# iot_hdmi_mux.net
KiCad netlist of a schematic drawn in Altium Designer
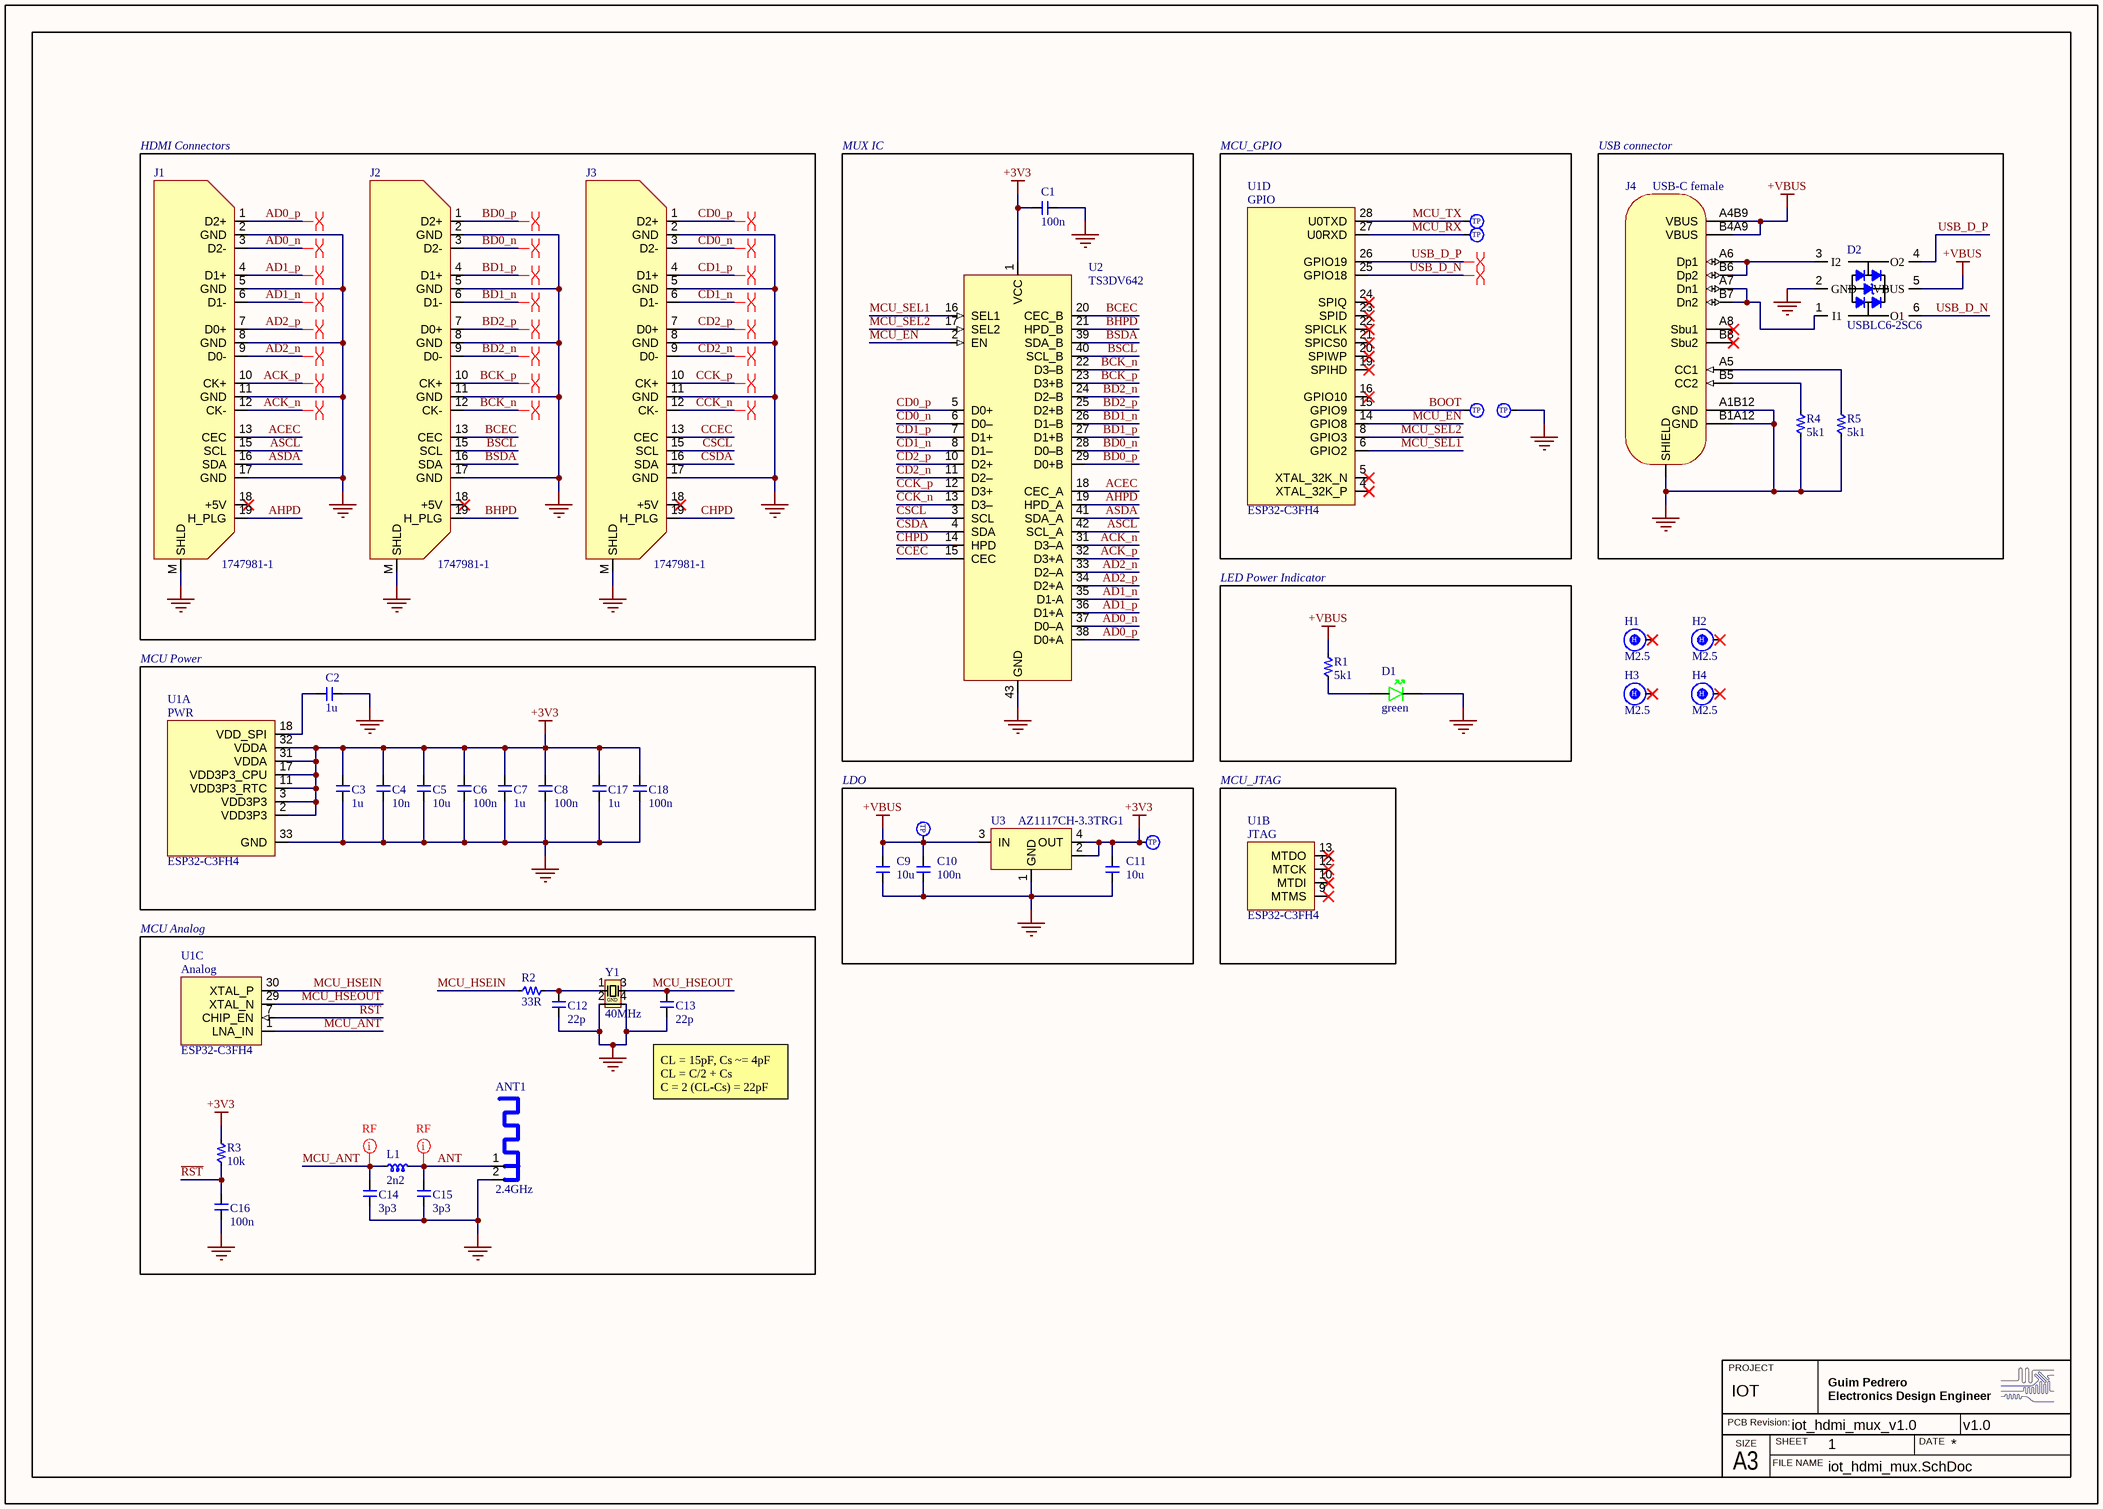
[diagram p0: iot_hdmi_mux.SchDoc]

(export (version "E")
  (design (tool "Eeschema 10.0.6"))
  (components
    (comp (ref "ANT1")
      (value "2.4GHz")
      (footprint "ANT_2.4")
      (description "SWRA117D 2.4GHz antenna design by TI")
      (libsource (lib "iot_hdmi_mux") (part "ANT_2.4"))
    )
    (comp (ref "C1")
      (value "100n")
      (footprint "C0402")
      (description "0402 cap")
      (libsource (lib "iot_hdmi_mux") (part "C_0402"))
    )
    (comp (ref "C2")
      (value "1u")
      (footprint "C0603")
      (description "0603 cap")
      (libsource (lib "iot_hdmi_mux") (part "C_0603"))
    )
    (comp (ref "C3")
      (value "1u")
      (footprint "C0603")
      (description "0603 cap")
      (libsource (lib "iot_hdmi_mux") (part "C_0603"))
    )
    (comp (ref "C4")
      (value "10n")
      (footprint "C0402")
      (description "0402 cap")
      (libsource (lib "iot_hdmi_mux") (part "C_0402"))
    )
    (comp (ref "C5")
      (value "10u")
      (footprint "C0603")
      (description "0603 cap")
      (libsource (lib "iot_hdmi_mux") (part "C_0603"))
    )
    (comp (ref "C6")
      (value "100n")
      (footprint "C0402")
      (description "0402 cap")
      (libsource (lib "iot_hdmi_mux") (part "C_0402"))
    )
    (comp (ref "C7")
      (value "1u")
      (footprint "C0603")
      (description "0603 cap")
      (libsource (lib "iot_hdmi_mux") (part "C_0603"))
    )
    (comp (ref "C8")
      (value "100n")
      (footprint "C0402")
      (description "0402 cap")
      (libsource (lib "iot_hdmi_mux") (part "C_0402"))
    )
    (comp (ref "C9")
      (value "10u")
      (footprint "C0402")
      (description "0402 cap")
      (libsource (lib "LinearDriver") (part "C_0402"))
    )
    (comp (ref "C10")
      (value "100n")
      (footprint "C0402")
      (description "0402 cap")
      (libsource (lib "LinearDriver") (part "C_0402"))
    )
    (comp (ref "C11")
      (value "10u")
      (footprint "C0402")
      (description "0402 cap")
      (libsource (lib "LinearDriver") (part "C_0402"))
    )
    (comp (ref "C12")
      (value "22p")
      (footprint "C0402")
      (description "0402 cap")
      (libsource (lib "FOC_Drive") (part "C_0402"))
    )
    (comp (ref "C13")
      (value "22p")
      (footprint "C0402")
      (description "0402 cap")
      (libsource (lib "FOC_Drive") (part "C_0402"))
    )
    (comp (ref "C14")
      (value "3p3")
      (footprint "C0402")
      (description "0402 cap")
      (libsource (lib "iot_hdmi_mux") (part "C_0402"))
    )
    (comp (ref "C15")
      (value "3p3")
      (footprint "C0402")
      (description "0402 cap")
      (libsource (lib "iot_hdmi_mux") (part "C_0402"))
    )
    (comp (ref "C16")
      (value "100n")
      (footprint "C0402")
      (description "0402 cap")
      (libsource (lib "iot_hdmi_mux") (part "C_0402"))
    )
    (comp (ref "C17")
      (value "1u")
      (footprint "C0603")
      (description "0603 cap")
      (libsource (lib "iot_hdmi_mux") (part "C_0603"))
    )
    (comp (ref "C18")
      (value "100n")
      (footprint "C0402")
      (description "0402 cap")
      (libsource (lib "iot_hdmi_mux") (part "C_0402"))
    )
    (comp (ref "D1")
      (value "green")
      (footprint "LED_0805_G")
      (description "0805 green LED")
      (libsource (lib "iot_hdmi_mux") (part "LED_0805_G"))
    )
    (comp (ref "D2")
      (value "USBLC6-2SC6")
      (footprint "USBLC6-2SC6")
      (description "Trans Voltage Suppressor Diode, 5V V(RWM), Unidirectional, 1 Element, Silicon")
      (fields (field (name "MANUFACTURER") "STMicroelectronics"))
      (libsource (lib "R20_PCBM") (part "USBLC6-2SC6"))
    )
    (comp (ref "H1")
      (value "M2.5")
      (footprint "M2.5_HOLE")
      (description "M2.5 hole with connection")
      (libsource (lib "iot_hdmi_mux") (part "M2.5_HOLE"))
    )
    (comp (ref "H2")
      (value "M2.5")
      (footprint "M2.5_HOLE")
      (description "M2.5 hole with connection")
      (libsource (lib "iot_hdmi_mux") (part "M2.5_HOLE"))
    )
    (comp (ref "H3")
      (value "M2.5")
      (footprint "M2.5_HOLE")
      (description "M2.5 hole with connection")
      (libsource (lib "iot_hdmi_mux") (part "M2.5_HOLE"))
    )
    (comp (ref "H4")
      (value "M2.5")
      (footprint "M2.5_HOLE")
      (description "M2.5 hole with connection")
      (libsource (lib "iot_hdmi_mux") (part "M2.5_HOLE"))
    )
    (comp (ref "J1")
      (value "1747981-1")
      (footprint "1747981-1")
      (description "HDMI (High-Definition Multimedia Interface) Connector; No Flange; Through hole")
      (fields (field (name "MANUFACTURER") "AMP - TE CONNECTIVITY"))
      (libsource (lib "iot_hdmi_mux") (part "1747981-1"))
    )
    (comp (ref "J2")
      (value "1747981-1")
      (footprint "1747981-1")
      (description "HDMI (High-Definition Multimedia Interface) Connector; No Flange; Through hole")
      (fields (field (name "MANUFACTURER") "AMP - TE CONNECTIVITY"))
      (libsource (lib "iot_hdmi_mux") (part "1747981-1"))
    )
    (comp (ref "J3")
      (value "1747981-1")
      (footprint "1747981-1")
      (description "HDMI (High-Definition Multimedia Interface) Connector; No Flange; Through hole")
      (fields (field (name "MANUFACTURER") "AMP - TE CONNECTIVITY"))
      (libsource (lib "iot_hdmi_mux") (part "1747981-1"))
    )
    (comp (ref "J4")
      (value "USB-C female")
      (footprint "TYPE-C-31-M-12")
      (description "Conn USB Type C PL 22 POS 0.5mm Solder ST SMD 22 Terminal 1Port Emboss T/R")
      (fields
        (field (name "MANUFACTURER") "HRO Electronics")
        (field (name "MANUFACTURER PART NUMBER") "TYPE-C-31-M-12")
      )
      (libsource (lib "rotor_magnetics_tb") (part "TYPE-C-31-M-12"))
    )
    (comp (ref "L1")
      (value "2n2")
      (footprint "L0402")
      (description "0402 inductor")
      (libsource (lib "iot_hdmi_mux") (part "L_0402"))
    )
    (comp (ref "R1")
      (value "5k1")
      (footprint "R0402")
      (description "0402 62.5mW")
      (libsource (lib "PCB_motor") (part "R_0402"))
    )
    (comp (ref "R2")
      (value "33R")
      (footprint "R0402")
      (description "0402 62.5mW")
      (libsource (lib "iot_hdmi_mux") (part "R_0402"))
    )
    (comp (ref "R3")
      (value "10k")
      (footprint "R0402")
      (description "0402 62.5mW")
      (libsource (lib "iot_hdmi_mux") (part "R_0402"))
    )
    (comp (ref "R4")
      (value "5k1")
      (footprint "R0402")
      (description "0402 62.5mW")
      (libsource (lib "PCB_motor") (part "R_0402"))
    )
    (comp (ref "R5")
      (value "5k1")
      (footprint "R0402")
      (description "0402 62.5mW")
      (libsource (lib "PCB_motor") (part "R_0402"))
    )
    (comp (ref "TP1")
      (value "Testing_Point_1mm")
      (footprint "TestingPoint_1mm")
      (description "1mm testing point")
      (libsource (lib "iot_hdmi_mux") (part "Testing_Point_1mm"))
    )
    (comp (ref "TP2")
      (value "Testing_Point_1mm")
      (footprint "TestingPoint_1mm")
      (description "1mm testing point")
      (libsource (lib "iot_hdmi_mux") (part "Testing_Point_1mm"))
    )
    (comp (ref "TP3")
      (value "Testing_Point_1mm")
      (footprint "TestingPoint_1mm")
      (description "1mm testing point")
      (libsource (lib "iot_hdmi_mux") (part "Testing_Point_1mm"))
    )
    (comp (ref "TP4")
      (value "Testing_Point_1mm")
      (footprint "TestingPoint_1mm")
      (description "1mm testing point")
      (libsource (lib "iot_hdmi_mux") (part "Testing_Point_1mm"))
    )
    (comp (ref "TP5")
      (value "Testing_Point_1mm")
      (footprint "TestingPoint_1mm")
      (description "1mm testing point")
      (libsource (lib "LinearDriver") (part "Testing_Point_1mm"))
    )
    (comp (ref "TP6")
      (value "Testing_Point_1mm")
      (footprint "TestingPoint_1mm")
      (description "1mm testing point")
      (libsource (lib "LinearDriver") (part "Testing_Point_1mm"))
    )
    (comp (ref "U1")
      (value "ESP32-C3FH4")
      (footprint "QFN50P500X500X90_HS-33N")
      (fields (field (name "MANUFACTURER") "Espressif Systems"))
      (libsource (lib "iot_hdmi_mux") (part "ESP32-C3FH4"))
    )
    (comp (ref "U2")
      (value "TS3DV642")
      (footprint "QFN50P350X900X80_HS-43N")
      (description "6-Gbps 12-channel differential 1-to-2 and 2-to-1 mux for DVI 1.0/ DisplayPort 1.4 /HDMI 2.0")
      (fields
        (field (name "MANUFACTURER") "Texas Instruments")
        (field (name "MANUFACTURER PART NUMBER") "TS3DV642A0RUAR")
      )
      (libsource (lib "iot_hdmi_mux") (part "TS3DV642"))
    )
    (comp (ref "U3")
      (value "AZ1117CH-3.3TRG1")
      (footprint "AZ1117CH-3.3TRG1")
      (description "Fixed Positive LDO Regulator, 3.3V, 1.3V Dropout, BIPolar, PDSO3")
      (fields (field (name "MANUFACTURER") "Diodes"))
      (libsource (lib "LinearDriver") (part "AZ1117CH-3.3TRG1"))
    )
    (comp (ref "Y1")
      (value "40MHz")
      (footprint "SMD3225-4P")
      (description "40MHz Surface Mount Crystal 15pF ±10ppm ±20ppm SMD3225-4P Crystals ROHS")
      (libsource (lib "iot_hdmi_mux") (part "X322540MPB4SI"))
    )
  )
  (nets
    (net (code "1") (name "+3V3") (class "Default")
      (node (ref "C1") (pin "2") (pinfunction "2_2") (pintype "passive"))
      (node (ref "C11") (pin "2") (pinfunction "2_2") (pintype "passive"))
      (node (ref "C17") (pin "2") (pinfunction "2_2") (pintype "passive"))
      (node (ref "C18") (pin "1") (pinfunction "1_1") (pintype "passive"))
      (node (ref "C3") (pin "2") (pinfunction "2_2") (pintype "passive"))
      (node (ref "C4") (pin "1") (pinfunction "1_1") (pintype "passive"))
      (node (ref "C5") (pin "2") (pinfunction "2_2") (pintype "passive"))
      (node (ref "C6") (pin "1") (pinfunction "1_1") (pintype "passive"))
      (node (ref "C7") (pin "2") (pinfunction "2_2") (pintype "passive"))
      (node (ref "C8") (pin "1") (pinfunction "1_1") (pintype "passive"))
      (node (ref "R3") (pin "2") (pinfunction "2_2") (pintype "passive"))
      (node (ref "TP6") (pin "1") (pinfunction "1_1") (pintype "passive"))
      (node (ref "U1") (pin "11") (pinfunction "VDD3P3_RTC_11") (pintype "power_in"))
      (node (ref "U1") (pin "17") (pinfunction "VDD3P3_CPU_17") (pintype "power_in"))
      (node (ref "U1") (pin "2") (pinfunction "VDD3P3_2") (pintype "power_in"))
      (node (ref "U1") (pin "3") (pinfunction "VDD3P3_3") (pintype "power_in"))
      (node (ref "U1") (pin "31") (pinfunction "VDDA_31") (pintype "power_in"))
      (node (ref "U1") (pin "32") (pinfunction "VDDA_32") (pintype "power_in"))
      (node (ref "U2") (pin "1") (pinfunction "VCC_1") (pintype "power_in"))
      (node (ref "U3") (pin "2") (pinfunction "OUT_2") (pintype "power_in"))
      (node (ref "U3") (pin "4") (pinfunction "OUT_4") (pintype "power_in"))
    )
    (net (code "2") (name "+VBUS") (class "Default")
      (node (ref "C10") (pin "2") (pinfunction "2_2") (pintype "passive"))
      (node (ref "C9") (pin "2") (pinfunction "2_2") (pintype "passive"))
      (node (ref "D2") (pin "5") (pinfunction "VBUS_5") (pintype "passive"))
      (node (ref "J4") (pin "A4B9") (pinfunction "VBUS_A4B9") (pintype "power_in"))
      (node (ref "J4") (pin "B4A9") (pinfunction "VBUS_B4A9") (pintype "power_in"))
      (node (ref "R1") (pin "2") (pinfunction "2_2") (pintype "passive"))
      (node (ref "TP5") (pin "1") (pinfunction "1_1") (pintype "passive"))
      (node (ref "U3") (pin "3") (pinfunction "IN_3") (pintype "power_in"))
    )
    (net (code "3") (name "/ACEC") (class "Default")
      (node (ref "J1") (pin "13") (pinfunction "CEC_13") (pintype "bidirectional"))
      (node (ref "U2") (pin "18") (pinfunction "CEC_A_18") (pintype "bidirectional"))
    )
    (net (code "4") (name "/ACK_n") (class "Default")
      (node (ref "J1") (pin "12") (pinfunction "CK-_12") (pintype "bidirectional"))
      (node (ref "U2") (pin "31") (pinfunction "D3–A_31") (pintype "bidirectional"))
    )
    (net (code "5") (name "/ACK_p") (class "Default")
      (node (ref "J1") (pin "10") (pinfunction "CK+_10") (pintype "bidirectional"))
      (node (ref "U2") (pin "32") (pinfunction "D3+A_32") (pintype "bidirectional"))
    )
    (net (code "6") (name "/AD0_n") (class "Default")
      (node (ref "J1") (pin "3") (pinfunction "D2-_3") (pintype "bidirectional"))
      (node (ref "U2") (pin "37") (pinfunction "D0–A_37") (pintype "bidirectional"))
    )
    (net (code "7") (name "/AD0_p") (class "Default")
      (node (ref "J1") (pin "1") (pinfunction "D2+_1") (pintype "bidirectional"))
      (node (ref "U2") (pin "38") (pinfunction "D0+A_38") (pintype "bidirectional"))
    )
    (net (code "8") (name "/AD1_n") (class "Default")
      (node (ref "J1") (pin "6") (pinfunction "D1-_6") (pintype "bidirectional"))
      (node (ref "U2") (pin "35") (pinfunction "D1-A_35") (pintype "bidirectional"))
    )
    (net (code "9") (name "/AD1_p") (class "Default")
      (node (ref "J1") (pin "4") (pinfunction "D1+_4") (pintype "bidirectional"))
      (node (ref "U2") (pin "36") (pinfunction "D1+A_36") (pintype "bidirectional"))
    )
    (net (code "10") (name "/AD2_n") (class "Default")
      (node (ref "J1") (pin "9") (pinfunction "D0-_9") (pintype "bidirectional"))
      (node (ref "U2") (pin "33") (pinfunction "D2–A_33") (pintype "bidirectional"))
    )
    (net (code "11") (name "/AD2_p") (class "Default")
      (node (ref "J1") (pin "7") (pinfunction "D0+_7") (pintype "bidirectional"))
      (node (ref "U2") (pin "34") (pinfunction "D2+A_34") (pintype "bidirectional"))
    )
    (net (code "12") (name "/AHPD") (class "Default")
      (node (ref "J1") (pin "19") (pinfunction "H_PLG_19") (pintype "bidirectional"))
      (node (ref "U2") (pin "19") (pinfunction "HPD_A_19") (pintype "bidirectional"))
    )
    (net (code "13") (name "/ANT") (class "Default")
      (node (ref "ANT1") (pin "1") (pinfunction "1_1") (pintype "passive"))
      (node (ref "C15") (pin "1") (pinfunction "1_1") (pintype "passive"))
      (node (ref "L1") (pin "2") (pinfunction "2_2") (pintype "passive"))
    )
    (net (code "14") (name "/ASCL") (class "Default")
      (node (ref "J1") (pin "15") (pinfunction "SCL_15") (pintype "bidirectional"))
      (node (ref "U2") (pin "42") (pinfunction "SCL_A_42") (pintype "bidirectional"))
    )
    (net (code "15") (name "/ASDA") (class "Default")
      (node (ref "J1") (pin "16") (pinfunction "SDA_16") (pintype "bidirectional"))
      (node (ref "U2") (pin "41") (pinfunction "SDA_A_41") (pintype "bidirectional"))
    )
    (net (code "16") (name "/BCEC") (class "Default")
      (node (ref "J2") (pin "13") (pinfunction "CEC_13") (pintype "bidirectional"))
      (node (ref "U2") (pin "20") (pinfunction "CEC_B_20") (pintype "bidirectional"))
    )
    (net (code "17") (name "/BCK_n") (class "Default")
      (node (ref "J2") (pin "12") (pinfunction "CK-_12") (pintype "bidirectional"))
      (node (ref "U2") (pin "22") (pinfunction "D3–B_22") (pintype "bidirectional"))
    )
    (net (code "18") (name "/BCK_p") (class "Default")
      (node (ref "J2") (pin "10") (pinfunction "CK+_10") (pintype "bidirectional"))
      (node (ref "U2") (pin "23") (pinfunction "D3+B_23") (pintype "bidirectional"))
    )
    (net (code "19") (name "/BD0_n") (class "Default")
      (node (ref "J2") (pin "3") (pinfunction "D2-_3") (pintype "bidirectional"))
      (node (ref "U2") (pin "28") (pinfunction "D0–B_28") (pintype "bidirectional"))
    )
    (net (code "20") (name "/BD0_p") (class "Default")
      (node (ref "J2") (pin "1") (pinfunction "D2+_1") (pintype "bidirectional"))
      (node (ref "U2") (pin "29") (pinfunction "D0+B_29") (pintype "bidirectional"))
    )
    (net (code "21") (name "/BD1_n") (class "Default")
      (node (ref "J2") (pin "6") (pinfunction "D1-_6") (pintype "bidirectional"))
      (node (ref "U2") (pin "26") (pinfunction "D1–B_26") (pintype "bidirectional"))
    )
    (net (code "22") (name "/BD1_p") (class "Default")
      (node (ref "J2") (pin "4") (pinfunction "D1+_4") (pintype "bidirectional"))
      (node (ref "U2") (pin "27") (pinfunction "D1+B_27") (pintype "bidirectional"))
    )
    (net (code "23") (name "/BD2_n") (class "Default")
      (node (ref "J2") (pin "9") (pinfunction "D0-_9") (pintype "bidirectional"))
      (node (ref "U2") (pin "24") (pinfunction "D2–B_24") (pintype "bidirectional"))
    )
    (net (code "24") (name "/BD2_p") (class "Default")
      (node (ref "J2") (pin "7") (pinfunction "D0+_7") (pintype "bidirectional"))
      (node (ref "U2") (pin "25") (pinfunction "D2+B_25") (pintype "bidirectional"))
    )
    (net (code "25") (name "/BHPD") (class "Default")
      (node (ref "J2") (pin "19") (pinfunction "H_PLG_19") (pintype "bidirectional"))
      (node (ref "U2") (pin "21") (pinfunction "HPD_B_21") (pintype "bidirectional"))
    )
    (net (code "26") (name "/BOOT") (class "Default")
      (node (ref "TP3") (pin "1") (pinfunction "1_1") (pintype "passive"))
      (node (ref "U1") (pin "15") (pinfunction "GPIO9_15") (pintype "bidirectional"))
    )
    (net (code "27") (name "/BSCL") (class "Default")
      (node (ref "J2") (pin "15") (pinfunction "SCL_15") (pintype "bidirectional"))
      (node (ref "U2") (pin "40") (pinfunction "SCL_B_40") (pintype "bidirectional"))
    )
    (net (code "28") (name "/BSDA") (class "Default")
      (node (ref "J2") (pin "16") (pinfunction "SDA_16") (pintype "bidirectional"))
      (node (ref "U2") (pin "39") (pinfunction "SDA_B_39") (pintype "bidirectional"))
    )
    (net (code "29") (name "/CCEC") (class "Default")
      (node (ref "J3") (pin "13") (pinfunction "CEC_13") (pintype "bidirectional"))
      (node (ref "U2") (pin "15") (pinfunction "CEC_15") (pintype "bidirectional"))
    )
    (net (code "30") (name "/CCK_n") (class "Default")
      (node (ref "J3") (pin "12") (pinfunction "CK-_12") (pintype "bidirectional"))
      (node (ref "U2") (pin "13") (pinfunction "D3–_13") (pintype "bidirectional"))
    )
    (net (code "31") (name "/CCK_p") (class "Default")
      (node (ref "J3") (pin "10") (pinfunction "CK+_10") (pintype "bidirectional"))
      (node (ref "U2") (pin "12") (pinfunction "D3+_12") (pintype "bidirectional"))
    )
    (net (code "32") (name "/CD0_n") (class "Default")
      (node (ref "J3") (pin "3") (pinfunction "D2-_3") (pintype "bidirectional"))
      (node (ref "U2") (pin "6") (pinfunction "D0–_6") (pintype "bidirectional"))
    )
    (net (code "33") (name "/CD0_p") (class "Default")
      (node (ref "J3") (pin "1") (pinfunction "D2+_1") (pintype "bidirectional"))
      (node (ref "U2") (pin "5") (pinfunction "D0+_5") (pintype "bidirectional"))
    )
    (net (code "34") (name "/CD1_n") (class "Default")
      (node (ref "J3") (pin "6") (pinfunction "D1-_6") (pintype "bidirectional"))
      (node (ref "U2") (pin "8") (pinfunction "D1–_8") (pintype "bidirectional"))
    )
    (net (code "35") (name "/CD1_p") (class "Default")
      (node (ref "J3") (pin "4") (pinfunction "D1+_4") (pintype "bidirectional"))
      (node (ref "U2") (pin "7") (pinfunction "D1+_7") (pintype "bidirectional"))
    )
    (net (code "36") (name "/CD2_n") (class "Default")
      (node (ref "J3") (pin "9") (pinfunction "D0-_9") (pintype "bidirectional"))
      (node (ref "U2") (pin "11") (pinfunction "D2–_11") (pintype "bidirectional"))
    )
    (net (code "37") (name "/CD2_p") (class "Default")
      (node (ref "J3") (pin "7") (pinfunction "D0+_7") (pintype "bidirectional"))
      (node (ref "U2") (pin "10") (pinfunction "D2+_10") (pintype "bidirectional"))
    )
    (net (code "38") (name "/CHPD") (class "Default")
      (node (ref "J3") (pin "19") (pinfunction "H_PLG_19") (pintype "bidirectional"))
      (node (ref "U2") (pin "14") (pinfunction "HPD_14") (pintype "bidirectional"))
    )
    (net (code "39") (name "/CSCL") (class "Default")
      (node (ref "J3") (pin "15") (pinfunction "SCL_15") (pintype "bidirectional"))
      (node (ref "U2") (pin "3") (pinfunction "SCL_3") (pintype "bidirectional"))
    )
    (net (code "40") (name "/CSDA") (class "Default")
      (node (ref "J3") (pin "16") (pinfunction "SDA_16") (pintype "bidirectional"))
      (node (ref "U2") (pin "4") (pinfunction "SDA_4") (pintype "bidirectional"))
    )
    (net (code "41") (name "/MCU_ANT") (class "Default")
      (node (ref "C14") (pin "1") (pinfunction "1_1") (pintype "passive"))
      (node (ref "L1") (pin "1") (pinfunction "1_1") (pintype "passive"))
      (node (ref "U1") (pin "1") (pinfunction "LNA_IN_1") (pintype "bidirectional"))
    )
    (net (code "42") (name "/MCU_EN") (class "Default")
      (node (ref "U1") (pin "14") (pinfunction "GPIO8_14") (pintype "bidirectional"))
      (node (ref "U2") (pin "2") (pinfunction "EN_2") (pintype "input"))
    )
    (net (code "43") (name "/MCU_HSEIN") (class "Default")
      (node (ref "R2") (pin "1") (pinfunction "1_1") (pintype "passive"))
      (node (ref "U1") (pin "30") (pinfunction "XTAL_P_30") (pintype "bidirectional"))
    )
    (net (code "44") (name "/MCU_HSEOUT") (class "Default")
      (node (ref "C13") (pin "2") (pinfunction "2_2") (pintype "passive"))
      (node (ref "U1") (pin "29") (pinfunction "XTAL_N_29") (pintype "bidirectional"))
      (node (ref "Y1") (pin "3") (pinfunction "3_3") (pintype "passive"))
    )
    (net (code "45") (name "/MCU_RX") (class "Default")
      (node (ref "TP2") (pin "1") (pinfunction "1_1") (pintype "passive"))
      (node (ref "U1") (pin "27") (pinfunction "U0RXD_27") (pintype "bidirectional"))
    )
    (net (code "46") (name "/MCU_SEL1") (class "Default")
      (node (ref "U1") (pin "6") (pinfunction "GPIO2_6") (pintype "bidirectional"))
      (node (ref "U2") (pin "16") (pinfunction "SEL1_16") (pintype "input"))
    )
    (net (code "47") (name "/MCU_SEL2") (class "Default")
      (node (ref "U1") (pin "8") (pinfunction "GPIO3_8") (pintype "bidirectional"))
      (node (ref "U2") (pin "17") (pinfunction "SEL2_17") (pintype "input"))
    )
    (net (code "48") (name "/MCU_TX") (class "Default")
      (node (ref "TP1") (pin "1") (pinfunction "1_1") (pintype "passive"))
      (node (ref "U1") (pin "28") (pinfunction "U0TXD_28") (pintype "bidirectional"))
    )
    (net (code "49") (name "/USB_D_N") (class "Default")
      (node (ref "D2") (pin "6") (pinfunction "O1_6") (pintype "passive"))
      (node (ref "U1") (pin "25") (pinfunction "GPIO18_25") (pintype "bidirectional"))
    )
    (net (code "50") (name "/USB_D_P") (class "Default")
      (node (ref "D2") (pin "4") (pinfunction "O2_4") (pintype "passive"))
      (node (ref "U1") (pin "26") (pinfunction "GPIO19_26") (pintype "bidirectional"))
    )
    (net (code "51") (name "/~{RST}") (class "Default")
      (node (ref "C16") (pin "1") (pinfunction "1_1") (pintype "passive"))
      (node (ref "R3") (pin "1") (pinfunction "1_1") (pintype "passive"))
      (node (ref "U1") (pin "7") (pinfunction "CHIP_EN_7") (pintype "input"))
    )
    (net (code "52") (name "GND") (class "Default")
      (node (ref "ANT1") (pin "2") (pinfunction "2_2") (pintype "passive"))
      (node (ref "C1") (pin "1") (pinfunction "1_1") (pintype "passive"))
      (node (ref "C10") (pin "1") (pinfunction "1_1") (pintype "passive"))
      (node (ref "C11") (pin "1") (pinfunction "1_1") (pintype "passive"))
      (node (ref "C12") (pin "1") (pinfunction "1_1") (pintype "passive"))
      (node (ref "C13") (pin "1") (pinfunction "1_1") (pintype "passive"))
      (node (ref "C14") (pin "2") (pinfunction "2_2") (pintype "passive"))
      (node (ref "C15") (pin "2") (pinfunction "2_2") (pintype "passive"))
      (node (ref "C16") (pin "2") (pinfunction "2_2") (pintype "passive"))
      (node (ref "C17") (pin "1") (pinfunction "1_1") (pintype "passive"))
      (node (ref "C18") (pin "2") (pinfunction "2_2") (pintype "passive"))
      (node (ref "C2") (pin "1") (pinfunction "1_1") (pintype "passive"))
      (node (ref "C3") (pin "1") (pinfunction "1_1") (pintype "passive"))
      (node (ref "C4") (pin "2") (pinfunction "2_2") (pintype "passive"))
      (node (ref "C5") (pin "1") (pinfunction "1_1") (pintype "passive"))
      (node (ref "C6") (pin "2") (pinfunction "2_2") (pintype "passive"))
      (node (ref "C7") (pin "1") (pinfunction "1_1") (pintype "passive"))
      (node (ref "C8") (pin "2") (pinfunction "2_2") (pintype "passive"))
      (node (ref "C9") (pin "1") (pinfunction "1_1") (pintype "passive"))
      (node (ref "D1") (pin "1") (pinfunction "1_1") (pintype "passive"))
      (node (ref "D2") (pin "2") (pinfunction "GND_2") (pintype "passive"))
      (node (ref "J1") (pin "11") (pinfunction "GND_11") (pintype "power_in"))
      (node (ref "J1") (pin "17") (pinfunction "GND_17") (pintype "power_in"))
      (node (ref "J1") (pin "2") (pinfunction "GND_2") (pintype "power_in"))
      (node (ref "J1") (pin "5") (pinfunction "GND_5") (pintype "power_in"))
      (node (ref "J1") (pin "8") (pinfunction "GND_8") (pintype "power_in"))
      (node (ref "J1") (pin "M") (pinfunction "SHLD_M") (pintype "power_in"))
      (node (ref "J2") (pin "11") (pinfunction "GND_11") (pintype "power_in"))
      (node (ref "J2") (pin "17") (pinfunction "GND_17") (pintype "power_in"))
      (node (ref "J2") (pin "2") (pinfunction "GND_2") (pintype "power_in"))
      (node (ref "J2") (pin "5") (pinfunction "GND_5") (pintype "power_in"))
      (node (ref "J2") (pin "8") (pinfunction "GND_8") (pintype "power_in"))
      (node (ref "J2") (pin "M") (pinfunction "SHLD_M") (pintype "power_in"))
      (node (ref "J3") (pin "11") (pinfunction "GND_11") (pintype "power_in"))
      (node (ref "J3") (pin "17") (pinfunction "GND_17") (pintype "power_in"))
      (node (ref "J3") (pin "2") (pinfunction "GND_2") (pintype "power_in"))
      (node (ref "J3") (pin "5") (pinfunction "GND_5") (pintype "power_in"))
      (node (ref "J3") (pin "8") (pinfunction "GND_8") (pintype "power_in"))
      (node (ref "J3") (pin "M") (pinfunction "SHLD_M") (pintype "power_in"))
      (node (ref "J4") (pin "A1B12") (pinfunction "GND_A1B12") (pintype "power_in"))
      (node (ref "J4") (pin "B1A12") (pinfunction "GND_B1A12") (pintype "power_in"))
      (node (ref "J4") (pin "M1") (pinfunction "SHIELD_M1") (pintype "passive"))
      (node (ref "R4") (pin "1") (pinfunction "1_1") (pintype "passive"))
      (node (ref "R5") (pin "1") (pinfunction "1_1") (pintype "passive"))
      (node (ref "TP4") (pin "1") (pinfunction "1_1") (pintype "passive"))
      (node (ref "U1") (pin "33") (pinfunction "GND_33") (pintype "power_in"))
      (node (ref "U2") (pin "43") (pinfunction "GND_43") (pintype "power_in"))
      (node (ref "U3") (pin "1") (pinfunction "GND_1") (pintype "power_in"))
      (node (ref "Y1") (pin "2") (pinfunction "2_2") (pintype "passive"))
      (node (ref "Y1") (pin "4") (pinfunction "4_4") (pintype "passive"))
    )
    (net (code "53") (name "Net-(C12-Pad2)") (class "Default")
      (node (ref "C12") (pin "2") (pinfunction "2_2") (pintype "passive"))
      (node (ref "R2") (pin "2") (pinfunction "2_2") (pintype "passive"))
      (node (ref "Y1") (pin "1") (pinfunction "1_1") (pintype "passive"))
    )
    (net (code "54") (name "Net-(D1-Pad2)") (class "Default")
      (node (ref "D1") (pin "2") (pinfunction "2_2") (pintype "passive"))
      (node (ref "R1") (pin "1") (pinfunction "1_1") (pintype "passive"))
    )
    (net (code "55") (name "Net-(D2-I1)") (class "Default")
      (node (ref "D2") (pin "1") (pinfunction "I1_1") (pintype "passive"))
      (node (ref "J4") (pin "A7") (pinfunction "Dn1_A7") (pintype "bidirectional"))
      (node (ref "J4") (pin "B7") (pinfunction "Dn2_B7") (pintype "bidirectional"))
    )
    (net (code "56") (name "Net-(D2-I2)") (class "Default")
      (node (ref "D2") (pin "3") (pinfunction "I2_3") (pintype "passive"))
      (node (ref "J4") (pin "A6") (pinfunction "Dp1_A6") (pintype "bidirectional"))
      (node (ref "J4") (pin "B6") (pinfunction "Dp2_B6") (pintype "bidirectional"))
    )
    (net (code "57") (name "Net-(J4-CC1)") (class "Default")
      (node (ref "J4") (pin "A5") (pinfunction "CC1_A5") (pintype "input"))
      (node (ref "R5") (pin "2") (pinfunction "2_2") (pintype "passive"))
    )
    (net (code "58") (name "Net-(J4-CC2)") (class "Default")
      (node (ref "J4") (pin "B5") (pinfunction "CC2_B5") (pintype "input"))
      (node (ref "R4") (pin "2") (pinfunction "2_2") (pintype "passive"))
    )
    (net (code "59") (name "Net-(U1A-VDD_SPI)") (class "Default")
      (node (ref "C2") (pin "2") (pinfunction "2_2") (pintype "passive"))
      (node (ref "U1") (pin "18") (pinfunction "VDD_SPI_18") (pintype "power_in"))
    )
    (net (code "60") (name "unconnected-(H1-Pad1)") (class "Default")
      (node (ref "H1") (pin "1") (pinfunction "1_1") (pintype "passive+no_connect"))
    )
    (net (code "61") (name "unconnected-(H2-Pad1)") (class "Default")
      (node (ref "H2") (pin "1") (pinfunction "1_1") (pintype "passive+no_connect"))
    )
    (net (code "62") (name "unconnected-(H3-Pad1)") (class "Default")
      (node (ref "H3") (pin "1") (pinfunction "1_1") (pintype "passive+no_connect"))
    )
    (net (code "63") (name "unconnected-(H4-Pad1)") (class "Default")
      (node (ref "H4") (pin "1") (pinfunction "1_1") (pintype "passive+no_connect"))
    )
    (net (code "64") (name "unconnected-(J1-+5V-Pad18)") (class "Default")
      (node (ref "J1") (pin "18") (pinfunction "+5V_18") (pintype "power_in+no_connect"))
    )
    (net (code "65") (name "unconnected-(J2-+5V-Pad18)") (class "Default")
      (node (ref "J2") (pin "18") (pinfunction "+5V_18") (pintype "power_in+no_connect"))
    )
    (net (code "66") (name "unconnected-(J3-+5V-Pad18)") (class "Default")
      (node (ref "J3") (pin "18") (pinfunction "+5V_18") (pintype "power_in+no_connect"))
    )
    (net (code "67") (name "unconnected-(J4-Sbu1-PadA8)") (class "Default")
      (node (ref "J4") (pin "A8") (pinfunction "Sbu1_A8") (pintype "passive+no_connect"))
    )
    (net (code "68") (name "unconnected-(J4-Sbu2-PadB8)") (class "Default")
      (node (ref "J4") (pin "B8") (pinfunction "Sbu2_B8") (pintype "passive+no_connect"))
    )
    (net (code "69") (name "unconnected-(U1B-MTCK-Pad12)") (class "Default")
      (node (ref "U1") (pin "12") (pinfunction "MTCK_12") (pintype "bidirectional+no_connect"))
    )
    (net (code "70") (name "unconnected-(U1B-MTDI-Pad10)") (class "Default")
      (node (ref "U1") (pin "10") (pinfunction "MTDI_10") (pintype "bidirectional+no_connect"))
    )
    (net (code "71") (name "unconnected-(U1B-MTDO-Pad13)") (class "Default")
      (node (ref "U1") (pin "13") (pinfunction "MTDO_13") (pintype "bidirectional+no_connect"))
    )
    (net (code "72") (name "unconnected-(U1B-MTMS-Pad9)") (class "Default")
      (node (ref "U1") (pin "9") (pinfunction "MTMS_9") (pintype "bidirectional+no_connect"))
    )
    (net (code "73") (name "unconnected-(U1D-GPIO10-Pad16)") (class "Default")
      (node (ref "U1") (pin "16") (pinfunction "GPIO10_16") (pintype "bidirectional+no_connect"))
    )
    (net (code "74") (name "unconnected-(U1D-SPICLK-Pad22)") (class "Default")
      (node (ref "U1") (pin "22") (pinfunction "SPICLK_22") (pintype "bidirectional+no_connect"))
    )
    (net (code "75") (name "unconnected-(U1D-SPICS0-Pad21)") (class "Default")
      (node (ref "U1") (pin "21") (pinfunction "SPICS0_21") (pintype "bidirectional+no_connect"))
    )
    (net (code "76") (name "unconnected-(U1D-SPID-Pad23)") (class "Default")
      (node (ref "U1") (pin "23") (pinfunction "SPID_23") (pintype "bidirectional+no_connect"))
    )
    (net (code "77") (name "unconnected-(U1D-SPIHD-Pad19)") (class "Default")
      (node (ref "U1") (pin "19") (pinfunction "SPIHD_19") (pintype "bidirectional+no_connect"))
    )
    (net (code "78") (name "unconnected-(U1D-SPIQ-Pad24)") (class "Default")
      (node (ref "U1") (pin "24") (pinfunction "SPIQ_24") (pintype "bidirectional+no_connect"))
    )
    (net (code "79") (name "unconnected-(U1D-SPIWP-Pad20)") (class "Default")
      (node (ref "U1") (pin "20") (pinfunction "SPIWP_20") (pintype "bidirectional+no_connect"))
    )
    (net (code "80") (name "unconnected-(U1D-XTAL_32K_N-Pad5)") (class "Default")
      (node (ref "U1") (pin "5") (pinfunction "XTAL_32K_N_5") (pintype "bidirectional+no_connect"))
    )
    (net (code "81") (name "unconnected-(U1D-XTAL_32K_P-Pad4)") (class "Default")
      (node (ref "U1") (pin "4") (pinfunction "XTAL_32K_P_4") (pintype "bidirectional+no_connect"))
    )
  )
)
